# Hydrophone_preamp_Main_schematic.net
KiCad netlist of a schematic drawn in Altium Designer
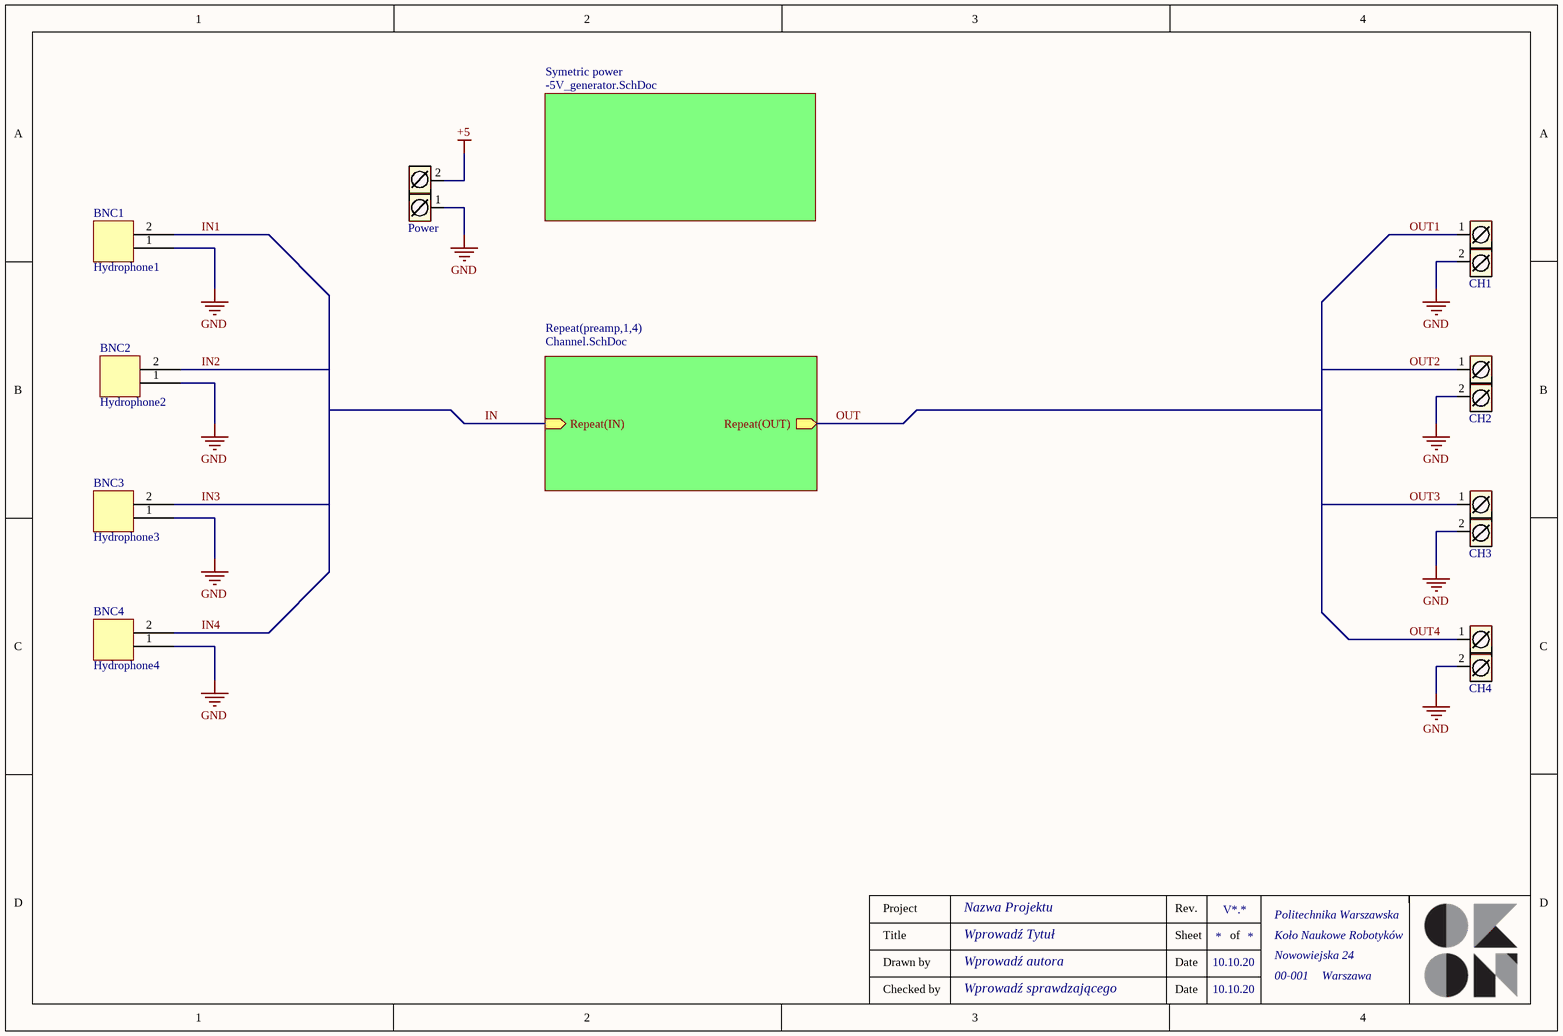
[diagram p0: Hydrophone_preamp_Main_schematic.SchDoc]

(export (version "E")
  (design (tool "Eeschema 10.0.6"))
  (components
    (comp (ref "BNC1")
      (value "Hydrophone1")
      (footprint "BNC")
      (libsource (lib "Sonar_OKOŃ") (part "BNC gniazdo"))
    )
    (comp (ref "BNC2")
      (value "Hydrophone2")
      (footprint "BNC")
      (libsource (lib "Sonar_OKOŃ") (part "BNC gniazdo"))
    )
    (comp (ref "BNC3")
      (value "Hydrophone3")
      (footprint "BNC")
      (libsource (lib "Sonar_OKOŃ") (part "BNC gniazdo"))
    )
    (comp (ref "BNC4")
      (value "Hydrophone4")
      (footprint "BNC")
      (libsource (lib "Sonar_OKOŃ") (part "BNC gniazdo"))
    )
    (comp (ref "CH1")
      (value "ARK2")
      (footprint "ARK2")
      (description "Złącze śrubowe 2 piny")
      (libsource (lib "") (part "ARK2_1"))
    )
    (comp (ref "CH2")
      (value "ARK2")
      (footprint "ARK2")
      (description "Złącze śrubowe 2 piny")
      (libsource (lib "") (part "ARK2_1"))
    )
    (comp (ref "CH3")
      (value "ARK2")
      (footprint "ARK2")
      (description "Złącze śrubowe 2 piny")
      (libsource (lib "") (part "ARK2_1"))
    )
    (comp (ref "CH4")
      (value "ARK2")
      (footprint "ARK2")
      (description "Złącze śrubowe 2 piny")
      (libsource (lib "") (part "ARK2_1"))
    )
    (comp (ref "Power")
      (value "ARK2")
      (footprint "ARK2")
      (description "Złącze śrubowe 2 piny")
      (libsource (lib "KNR_Kurs") (part "ARK2"))
    )
  )
  (nets
    (net (code "1") (name "+5") (class "Default")
      (node (ref "Power") (pin "2") (pinfunction "2_2") (pintype "passive"))
    )
    (net (code "3") (name "/IN1") (class "Default") (node (ref "BNC1") (pin "2") (pintype "passive")))
    (net (code "4") (name "/IN2") (class "Default") (node (ref "BNC2") (pin "2") (pintype "passive")))
    (net (code "5") (name "/IN3") (class "Default") (node (ref "BNC3") (pin "2") (pintype "passive")))
    (net (code "6") (name "/IN4") (class "Default") (node (ref "BNC4") (pin "2") (pintype "passive")))
    (net (code "8") (name "/OUT1") (class "Default")
      (node (ref "CH1") (pin "1") (pinfunction "1_1") (pintype "passive"))
    )
    (net (code "9") (name "/OUT2") (class "Default")
      (node (ref "CH2") (pin "1") (pinfunction "1_1") (pintype "passive"))
    )
    (net (code "10") (name "/OUT3") (class "Default")
      (node (ref "CH3") (pin "1") (pinfunction "1_1") (pintype "passive"))
    )
    (net (code "11") (name "/OUT4") (class "Default")
      (node (ref "CH4") (pin "1") (pinfunction "1_1") (pintype "passive"))
    )
    (net (code "12") (name "GND") (class "Default")
      (node (ref "BNC1") (pin "1") (pintype "passive"))
      (node (ref "BNC2") (pin "1") (pintype "passive"))
      (node (ref "BNC3") (pin "1") (pintype "passive"))
      (node (ref "BNC4") (pin "1") (pintype "passive"))
      (node (ref "CH1") (pin "2") (pinfunction "2_2") (pintype "passive"))
      (node (ref "CH2") (pin "2") (pinfunction "2_2") (pintype "passive"))
      (node (ref "CH3") (pin "2") (pinfunction "2_2") (pintype "passive"))
      (node (ref "CH4") (pin "2") (pinfunction "2_2") (pintype "passive"))
      (node (ref "Power") (pin "1") (pinfunction "1_1") (pintype "passive"))
    )
  )
)
